# NRF24l01_Breakout.net
KiCad netlist of a schematic drawn in EAGLE
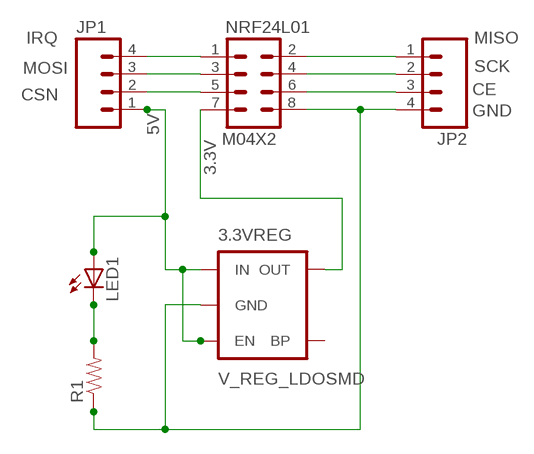
[diagram p0: schematic, sheet 1]

(export (version "E")
  (design (tool "Eeschema 10.0.6"))
  (components
    (comp (ref "3.3VREG")
      (value "V_REG_LDOSMD")
      (footprint "eagle-import:SOT23-5")
      (libsource (lib "eagle-import") (part "V_REG_LDOSMD"))
    )
    (comp (ref "JP1")
      (value "M04LOCK")
      (footprint "eagle-import:1X04_LOCK")
      (libsource (lib "eagle-import") (part "M04LOCK"))
    )
    (comp (ref "JP2")
      (value "M04LOCK")
      (footprint "eagle-import:1X04_LOCK")
      (libsource (lib "eagle-import") (part "M04LOCK"))
    )
    (comp (ref "LED1")
      (value "LED0603")
      (footprint "eagle-import:LED-0603")
      (libsource (lib "eagle-import") (part "LED0603"))
    )
    (comp (ref "NRF24L01")
      (value "M04X2")
      (footprint "eagle-import:2X4")
      (libsource (lib "eagle-import") (part "M04X2"))
    )
    (comp (ref "R1")
      (value "RESISTOR0805-RES")
      (footprint "eagle-import:0805")
      (libsource (lib "eagle-import") (part "RESISTOR0805-RES"))
    )
  )
  (nets
    (net (code "1") (name "/3.3V") (class "Default")
      (node (ref "3.3VREG") (pin "5") (pinfunction "OUT_5") (pintype "passive"))
      (node (ref "NRF24L01") (pin "7") (pinfunction "7_7") (pintype "passive"))
    )
    (net (code "2") (name "/5V") (class "Default")
      (node (ref "3.3VREG") (pin "1") (pinfunction "IN_1") (pintype "input"))
      (node (ref "3.3VREG") (pin "3") (pinfunction "EN_3") (pintype "input"))
      (node (ref "JP1") (pin "1") (pinfunction "1_1") (pintype "passive"))
      (node (ref "LED1") (pin "A") (pinfunction "A_A") (pintype "passive"))
    )
    (net (code "3") (name "/CE") (class "Default")
      (node (ref "JP2") (pin "3") (pinfunction "3_3") (pintype "passive"))
      (node (ref "NRF24L01") (pin "6") (pinfunction "6_6") (pintype "passive"))
    )
    (net (code "4") (name "/CSN") (class "Default")
      (node (ref "JP1") (pin "2") (pinfunction "2_2") (pintype "passive"))
      (node (ref "NRF24L01") (pin "5") (pinfunction "5_5") (pintype "passive"))
    )
    (net (code "5") (name "/GND") (class "Default")
      (node (ref "3.3VREG") (pin "2") (pinfunction "GND_2") (pintype "input"))
      (node (ref "JP2") (pin "4") (pinfunction "4_4") (pintype "passive"))
      (node (ref "NRF24L01") (pin "8") (pinfunction "8_8") (pintype "passive"))
      (node (ref "R1") (pin "1") (pinfunction "1_1") (pintype "passive"))
    )
    (net (code "6") (name "/IRQ") (class "Default")
      (node (ref "JP1") (pin "4") (pinfunction "4_4") (pintype "passive"))
      (node (ref "NRF24L01") (pin "1") (pinfunction "1_1") (pintype "passive"))
    )
    (net (code "7") (name "/MISO") (class "Default")
      (node (ref "JP2") (pin "1") (pinfunction "1_1") (pintype "passive"))
      (node (ref "NRF24L01") (pin "2") (pinfunction "2_2") (pintype "passive"))
    )
    (net (code "8") (name "/MOSI") (class "Default")
      (node (ref "JP1") (pin "3") (pinfunction "3_3") (pintype "passive"))
      (node (ref "NRF24L01") (pin "3") (pinfunction "3_3") (pintype "passive"))
    )
    (net (code "9") (name "/SCK") (class "Default")
      (node (ref "JP2") (pin "2") (pinfunction "2_2") (pintype "passive"))
      (node (ref "NRF24L01") (pin "4") (pinfunction "4_4") (pintype "passive"))
    )
    (net (code "10") (name "Net-(LED1-PadC)") (class "Default")
      (node (ref "LED1") (pin "C") (pinfunction "C_C") (pintype "passive"))
      (node (ref "R1") (pin "2") (pinfunction "2_2") (pintype "passive"))
    )
    (net (code "11") (name "unconnected-(3.3VREG-BP-Pad4)") (class "Default")
      (node (ref "3.3VREG") (pin "4") (pinfunction "BP_4") (pintype "input"))
    )
  )
)
